# S7V10Logger.net
KiCad netlist of a schematic drawn in Altium Designer
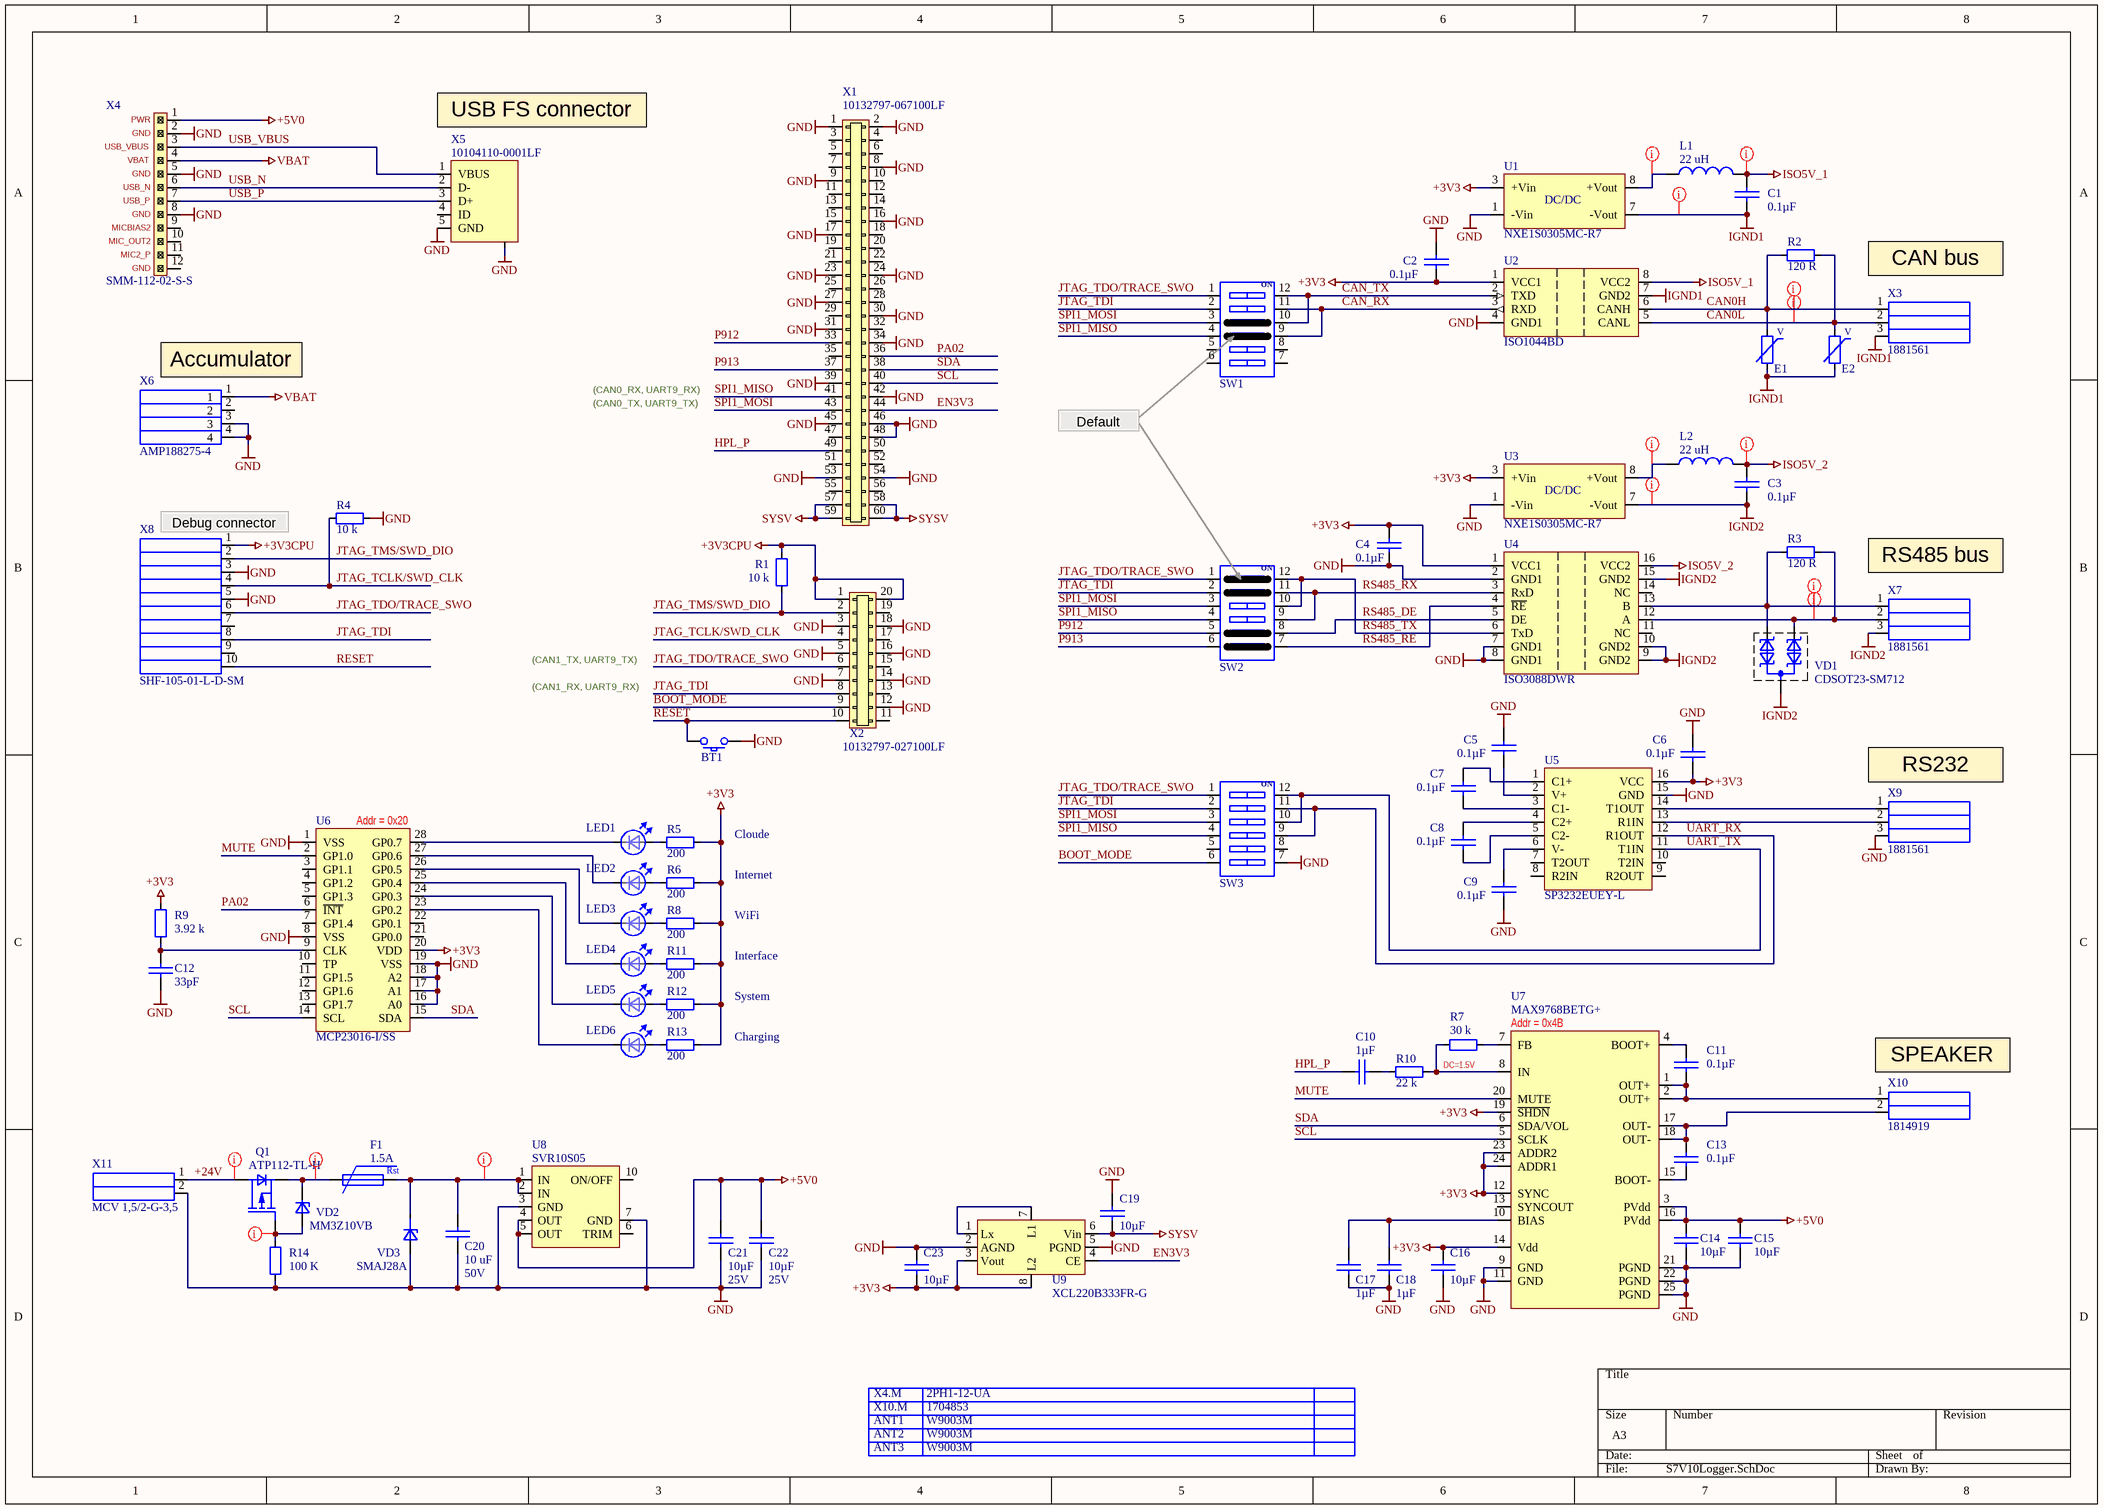
[diagram p0: S7V10Logger.SchDoc]

(export (version "E")
  (design (tool "Eeschema 10.0.6"))
  (components
    (comp (ref "ANT1")
      (value "W9003M")
      (description "CBL ASSY SMA-UMCC JACK-I-PEX 3\"")
      (fields
        (field (name "MANUFACTURER") "PulseLarsen Antennas")
        (field (name "PARTNAME") "W9003M")
        (field (name "PARTNUM") "1837-1025-ND")
      )
      (libsource (lib "ea_Mechanical") (part "BOM item"))
    )
    (comp (ref "ANT2")
      (value "W9003M")
      (description "CBL ASSY SMA-UMCC JACK-I-PEX 3\"")
      (fields
        (field (name "MANUFACTURER") "PulseLarsen Antennas")
        (field (name "PARTNAME") "W9003M")
        (field (name "PARTNUM") "1837-1025-ND")
      )
      (libsource (lib "ea_Mechanical") (part "BOM item"))
    )
    (comp (ref "ANT3")
      (value "W9003M")
      (description "CBL ASSY SMA-UMCC JACK-I-PEX 3\"")
      (fields
        (field (name "MANUFACTURER") "PulseLarsen Antennas")
        (field (name "PARTNAME") "W9003M")
        (field (name "PARTNUM") "1837-1025-ND")
      )
      (libsource (lib "ea_Mechanical") (part "BOM item"))
    )
    (comp (ref "BT1")
      (value "B3U-3000P")
      (footprint "B3U-3000P")
      (description "Tactile Switch SPST-NO Side Actuated Surface Mount, Right Angle")
      (fields
        (field (name "MANUFACTURER") "Omron Electronics Inc-EMC Div")
        (field (name "PARTNUM") "SW1022CT-ND")
      )
      (libsource (lib "ea_Buttons") (part "B3U-3000P"))
    )
    (comp (ref "C1")
      (value "0.1µF")
      (footprint "0603 CAP")
      (description "0.1µF, ±10%, 16V, X7R, 0603 (1608 Metric), -55°C ~ 125°C, -, General Purpose")
      (fields (field (name "TOLERANCE") "±10%") (field (name "MANUFACTURER") "Samsung Electro-Mechanics"))
      (libsource (lib "ea_PassivComps") (part "Capacitor"))
    )
    (comp (ref "C2")
      (value "0.1µF")
      (footprint "0603 CAP")
      (description "0.1µF, ±10%, 16V, X7R, 0603 (1608 Metric), -55°C ~ 125°C, -, General Purpose")
      (fields (field (name "TOLERANCE") "±10%") (field (name "MANUFACTURER") "Samsung Electro-Mechanics"))
      (libsource (lib "ea_PassivComps") (part "Capacitor"))
    )
    (comp (ref "C3")
      (value "0.1µF")
      (footprint "0603 CAP")
      (description "0.1µF, ±10%, 16V, X7R, 0603 (1608 Metric), -55°C ~ 125°C, -, General Purpose")
      (fields (field (name "TOLERANCE") "±10%") (field (name "MANUFACTURER") "Samsung Electro-Mechanics"))
      (libsource (lib "ea_PassivComps") (part "Capacitor"))
    )
    (comp (ref "C4")
      (value "0.1µF")
      (footprint "0603 CAP")
      (description "0.1µF, ±10%, 16V, X7R, 0603 (1608 Metric), -55°C ~ 125°C, -, General Purpose")
      (fields (field (name "TOLERANCE") "±10%") (field (name "MANUFACTURER") "Samsung Electro-Mechanics"))
      (libsource (lib "ea_PassivComps") (part "Capacitor"))
    )
    (comp (ref "C5")
      (value "0.1µF")
      (footprint "0603 CAP")
      (description "0.1µF, ±10%, 16V, X7R, 0603 (1608 Metric), -55°C ~ 125°C, -, General Purpose")
      (fields (field (name "TOLERANCE") "±10%") (field (name "MANUFACTURER") "Samsung Electro-Mechanics"))
      (libsource (lib "ea_PassivComps") (part "Capacitor"))
    )
    (comp (ref "C6")
      (value "0.1µF")
      (footprint "0603 CAP")
      (description "0.1µF, ±10%, 16V, X7R, 0603 (1608 Metric), -55°C ~ 125°C, -, General Purpose")
      (fields (field (name "TOLERANCE") "±10%") (field (name "MANUFACTURER") "Samsung Electro-Mechanics"))
      (libsource (lib "ea_PassivComps") (part "Capacitor"))
    )
    (comp (ref "C7")
      (value "0.1µF")
      (footprint "0603 CAP")
      (description "0.1µF, ±10%, 16V, X7R, 0603 (1608 Metric), -55°C ~ 125°C, -, General Purpose")
      (fields (field (name "TOLERANCE") "±10%") (field (name "MANUFACTURER") "Samsung Electro-Mechanics"))
      (libsource (lib "ea_PassivComps") (part "Capacitor"))
    )
    (comp (ref "C8")
      (value "0.1µF")
      (footprint "0603 CAP")
      (description "0.1µF, ±10%, 16V, X7R, 0603 (1608 Metric), -55°C ~ 125°C, -, General Purpose")
      (fields (field (name "TOLERANCE") "±10%") (field (name "MANUFACTURER") "Samsung Electro-Mechanics"))
      (libsource (lib "ea_PassivComps") (part "Capacitor"))
    )
    (comp (ref "C9")
      (value "0.1µF")
      (footprint "0603 CAP")
      (description "0.1µF, ±10%, 16V, X7R, 0603 (1608 Metric), -55°C ~ 125°C, -, General Purpose")
      (fields (field (name "TOLERANCE") "±10%") (field (name "MANUFACTURER") "Samsung Electro-Mechanics"))
      (libsource (lib "ea_PassivComps") (part "Capacitor"))
    )
    (comp (ref "C10")
      (value "1µF")
      (footprint "0603 CAP")
      (description "1µF, ±20%, 10V, X5R, 0603 (1608 Metric), -55°C ~ 85°C, -, General Purpose")
      (fields
        (field (name "PART NUMBER") "CL10A105MP8NNNC")
        (field (name "MANUFACTURER") "Samsung Electro-Mechanics")
      )
      (libsource (lib "ea_PassivComps") (part "Capacitor"))
    )
    (comp (ref "C11")
      (value "0.1µF")
      (footprint "0603 CAP")
      (description "0.1µF, ±10%, 16V, X7R, 0603 (1608 Metric), -55°C ~ 125°C, -, General Purpose")
      (fields (field (name "TOLERANCE") "±10%") (field (name "MANUFACTURER") "Samsung Electro-Mechanics"))
      (libsource (lib "ea_PassivComps") (part "Capacitor"))
    )
    (comp (ref "C12")
      (value "33pF")
      (footprint "0603 CAP")
      (description "33pF, ±5%, 25V, C0G, NP0, 0603 (1608 Metric), -55°C ~ 125°C, -, General Purpose")
      (fields
        (field (name "PART NUMBER") "885012006035")
        (field (name "MANUFACTURER") "Wurth Electronics Inc.")
      )
      (libsource (lib "ea_PassivComps") (part "Capacitor"))
    )
    (comp (ref "C13")
      (value "0.1µF")
      (footprint "0603 CAP")
      (description "0.1µF, ±10%, 16V, X7R, 0603 (1608 Metric), -55°C ~ 125°C, -, General Purpose")
      (fields (field (name "TOLERANCE") "±10%") (field (name "MANUFACTURER") "Samsung Electro-Mechanics"))
      (libsource (lib "ea_PassivComps") (part "Capacitor"))
    )
    (comp (ref "C14")
      (value "10µF")
      (footprint "0805 CAP")
      (description "10µF, ±20%, 16V, X5R, 0805 (2012 Metric), -55°C ~ 85°C, -, SMPS Filtering")
      (fields (field (name "PART NUMBER") "EMK212ABJ106MG-T") (field (name "MANUFACTURER") "Taiyo Yuden"))
      (libsource (lib "ea_PassivComps") (part "Capacitor"))
    )
    (comp (ref "C15")
      (value "10µF")
      (footprint "0805 CAP")
      (description "10µF, ±20%, 16V, X5R, 0805 (2012 Metric), -55°C ~ 85°C, -, SMPS Filtering")
      (fields (field (name "PART NUMBER") "EMK212ABJ106MG-T") (field (name "MANUFACTURER") "Taiyo Yuden"))
      (libsource (lib "ea_PassivComps") (part "Capacitor"))
    )
    (comp (ref "C16")
      (value "10µF")
      (footprint "0805 CAP")
      (description "10µF, ±20%, 16V, X5R, 0805 (2012 Metric), -55°C ~ 85°C, -, SMPS Filtering")
      (fields (field (name "PART NUMBER") "EMK212ABJ106MG-T") (field (name "MANUFACTURER") "Taiyo Yuden"))
      (libsource (lib "ea_PassivComps") (part "Capacitor"))
    )
    (comp (ref "C17")
      (value "1µF")
      (footprint "0603 CAP")
      (description "1µF, ±20%, 10V, X5R, 0603 (1608 Metric), -55°C ~ 85°C, -, General Purpose")
      (fields
        (field (name "PART NUMBER") "CL10A105MP8NNNC")
        (field (name "MANUFACTURER") "Samsung Electro-Mechanics")
      )
      (libsource (lib "ea_PassivComps") (part "Capacitor"))
    )
    (comp (ref "C18")
      (value "1µF")
      (footprint "0603 CAP")
      (description "1µF, ±20%, 10V, X5R, 0603 (1608 Metric), -55°C ~ 85°C, -, General Purpose")
      (fields
        (field (name "PART NUMBER") "CL10A105MP8NNNC")
        (field (name "MANUFACTURER") "Samsung Electro-Mechanics")
      )
      (libsource (lib "ea_PassivComps") (part "Capacitor"))
    )
    (comp (ref "C19")
      (value "10µF")
      (footprint "0805 CAP")
      (description "10µF, ±20%, 16V, X5R, 0805 (2012 Metric), -55°C ~ 85°C, -, SMPS Filtering")
      (fields (field (name "PART NUMBER") "EMK212ABJ106MG-T") (field (name "MANUFACTURER") "Taiyo Yuden"))
      (libsource (lib "ea_PassivComps") (part "Capacitor"))
    )
    (comp (ref "C20")
      (value "10 uF")
      (footprint "3225[1210]")
      (description "10uF, 50V, 20%, Y5V (F), 1210")
      (fields
        (field (name "MANUFACTURER") "Taiyo Yuden")
        (field (name "TOLERANCE") "20%")
        (field (name "VOLTAGE") "50V")
      )
      (libsource (lib "ea_Capacitors") (part "GRM32DF51H106ZA01L"))
    )
    (comp (ref "C21")
      (value "10µF")
      (footprint "1206 CAP")
      (description "10µF, ±10%, 25V, X5R, 1206 (3216 Metric), -55°C ~ 85°C, -, General Purpose")
      (fields
        (field (name "PART NUMBER") "CL31A106KAHNFNE")
        (field (name "MANUFACTURER") "Samsung Electro-Mechanics")
        (field (name "VOLTAGE - RATED") "25V")
      )
      (libsource (lib "ea_PassivComps") (part "Capacitor"))
    )
    (comp (ref "C22")
      (value "10µF")
      (footprint "1206 CAP")
      (description "10µF, ±10%, 25V, X5R, 1206 (3216 Metric), -55°C ~ 85°C, -, General Purpose")
      (fields
        (field (name "PART NUMBER") "CL31A106KAHNFNE")
        (field (name "MANUFACTURER") "Samsung Electro-Mechanics")
        (field (name "VOLTAGE - RATED") "25V")
      )
      (libsource (lib "ea_PassivComps") (part "Capacitor"))
    )
    (comp (ref "C23")
      (value "10µF")
      (footprint "0805 CAP")
      (description "10µF, ±20%, 16V, X5R, 0805 (2012 Metric), -55°C ~ 85°C, -, SMPS Filtering")
      (fields (field (name "PART NUMBER") "EMK212ABJ106MG-T") (field (name "MANUFACTURER") "Taiyo Yuden"))
      (libsource (lib "ea_PassivComps") (part "Capacitor"))
    )
    (comp (ref "E1")
      (value "823 560 505 60")
      (footprint "0603")
      (description "SUPPRESSOR ESD 5VDC, 56pF,  0603, -40..+85C")
      (fields (field (name "MANUFACTURER") "Würth Elektronik") (field (name "VOLTAGE") "5V"))
      (libsource (lib "ea_TVS_protection") (part "823 560 501 01"))
    )
    (comp (ref "E2")
      (value "823 560 505 60")
      (footprint "0603")
      (description "SUPPRESSOR ESD 5VDC, 56pF,  0603, -40..+85C")
      (fields (field (name "MANUFACTURER") "Würth Elektronik") (field (name "VOLTAGE") "5V"))
      (libsource (lib "ea_TVS_protection") (part "823 560 501 01"))
    )
    (comp (ref "F1")
      (value "1.5A")
      (footprint "2920 (7351 Metric)")
      (description "PTC RESETTABLE 60V 750MA, It=1.5A, 0.3s 2920(7351)")
      (fields (field (name "MANUFACTURER") "Bel Fuse Inc.") (field (name "PARTNUM") "507-1743-1-ND"))
      (libsource (lib "ea_Fuses") (part "0ZCF0075AF2C"))
    )
    (comp (ref "L1")
      (value "22 uH")
      (footprint "8200 Series Murata")
      (description "22uH, 320 mA, 0.92 Ohm, +-10%,- 40..85 C")
      (fields (field (name "MANUFACTURER") "TDK Corporation") (field (name "PARTNUM") "811-2475-1-ND"))
      (libsource (lib "ea_Inductors") (part "82223C"))
    )
    (comp (ref "L2")
      (value "22 uH")
      (footprint "8200 Series Murata")
      (description "22uH, 320 mA, 0.92 Ohm, +-10%,- 40..85 C")
      (fields (field (name "MANUFACTURER") "TDK Corporation") (field (name "PARTNUM") "811-2475-1-ND"))
      (libsource (lib "ea_Inductors") (part "82223C"))
    )
    (comp (ref "LED1")
      (value "SSL-LXA228SIC-TR31")
      (footprint "SSL-LXA228SIC-TR31")
      (description "LED RED CLEAR 2SMD REV, 20mA, 2V, 475 mcd, 1.9 mm")
      (fields (field (name "MANUFACTURER") "EVERLIGHT") (field (name "PARTNUM") "67-2243-1-ND"))
      (libsource (lib "ea_Indicators") (part "SSL-LXA228SIC-TR31"))
    )
    (comp (ref "LED2")
      (value "SSL-LXA228SIC-TR31")
      (footprint "SSL-LXA228SIC-TR31")
      (description "LED RED CLEAR 2SMD REV, 20mA, 2V, 475 mcd, 1.9 mm")
      (fields (field (name "MANUFACTURER") "EVERLIGHT") (field (name "PARTNUM") "67-2243-1-ND"))
      (libsource (lib "ea_Indicators") (part "SSL-LXA228SIC-TR31"))
    )
    (comp (ref "LED3")
      (value "SSL-LXA228SIC-TR31")
      (footprint "SSL-LXA228SIC-TR31")
      (description "LED RED CLEAR 2SMD REV, 20mA, 2V, 475 mcd, 1.9 mm")
      (fields (field (name "MANUFACTURER") "EVERLIGHT") (field (name "PARTNUM") "67-2243-1-ND"))
      (libsource (lib "ea_Indicators") (part "SSL-LXA228SIC-TR31"))
    )
    (comp (ref "LED4")
      (value "SSL-LXA228SIC-TR31")
      (footprint "SSL-LXA228SIC-TR31")
      (description "LED RED CLEAR 2SMD REV, 20mA, 2V, 475 mcd, 1.9 mm")
      (fields (field (name "MANUFACTURER") "EVERLIGHT") (field (name "PARTNUM") "67-2243-1-ND"))
      (libsource (lib "ea_Indicators") (part "SSL-LXA228SIC-TR31"))
    )
    (comp (ref "LED5")
      (value "SSL-LXA228SIC-TR31")
      (footprint "SSL-LXA228SIC-TR31")
      (description "LED RED CLEAR 2SMD REV, 20mA, 2V, 475 mcd, 1.9 mm")
      (fields (field (name "MANUFACTURER") "EVERLIGHT") (field (name "PARTNUM") "67-2243-1-ND"))
      (libsource (lib "ea_Indicators") (part "SSL-LXA228SIC-TR31"))
    )
    (comp (ref "LED6")
      (value "SSL-LXA228SIC-TR31")
      (footprint "SSL-LXA228SIC-TR31")
      (description "LED RED CLEAR 2SMD REV, 20mA, 2V, 475 mcd, 1.9 mm")
      (fields (field (name "MANUFACTURER") "EVERLIGHT") (field (name "PARTNUM") "67-2243-1-ND"))
      (libsource (lib "ea_Indicators") (part "SSL-LXA228SIC-TR31"))
    )
    (comp (ref "Q1")
      (value "ATP112-TL-H")
      (footprint "ATPAK, On Semiconductor")
      (description "P-Channel MOSFET, –25 A, –20 V, RDS(ON) = 0.04,  VGS = –10 V")
      (fields (field (name "MANUFACTURER") "ON Semiconductor") (field (name "PARTNUM") "ATP112-TL-HOSCT-ND"))
      (libsource (lib "ea_MOSFET_&_drivers") (part "ATP112-TL-H"))
    )
    (comp (ref "R1")
      (value "10 k")
      (footprint "0603")
      (fields
        (field (name "MANUFACTURER") "Bourns Inc.")
        (field (name "TOLERANCE") "±1%")
        (field (name "VOLTAGE") "75V")
      )
      (libsource (lib "") (part "Resistor_1"))
    )
    (comp (ref "R2")
      (value "120 R")
      (footprint "0603")
      (description "120 R, 1%, 0603, SMD Resistor, Taped")
      (fields (field (name "MANUFACTURER") "Vishay") (field (name "TOLERANCE") "±1%"))
      (libsource (lib "ea_Resistors") (part "RL0603E120-1"))
    )
    (comp (ref "R3")
      (value "120 R")
      (footprint "0603")
      (description "120 R, 1%, 0603, SMD Resistor, Taped")
      (fields (field (name "MANUFACTURER") "Vishay") (field (name "TOLERANCE") "±1%"))
      (libsource (lib "ea_Resistors") (part "RL0603E120-1"))
    )
    (comp (ref "R4")
      (value "10 k")
      (footprint "0603")
      (fields
        (field (name "MANUFACTURER") "Bourns Inc.")
        (field (name "TOLERANCE") "±1%")
        (field (name "VOLTAGE") "75V")
      )
      (libsource (lib "ea_PassivComps") (part "Resistor"))
    )
    (comp (ref "R5")
      (value "200")
      (footprint "0603")
      (fields
        (field (name "MANUFACTURER") "Stackpole Electronics Inc.")
        (field (name "TOLERANCE") "±1%")
        (field (name "VOLTAGE") "75V")
      )
      (libsource (lib "ea_PassivComps") (part "Resistor"))
    )
    (comp (ref "R6")
      (value "200")
      (footprint "0603")
      (fields
        (field (name "MANUFACTURER") "Stackpole Electronics Inc.")
        (field (name "TOLERANCE") "±1%")
        (field (name "VOLTAGE") "75V")
      )
      (libsource (lib "ea_PassivComps") (part "Resistor"))
    )
    (comp (ref "R7")
      (value "30 k")
      (footprint "0603")
      (fields
        (field (name "MANUFACTURER") "Stackpole Electronics Inc.")
        (field (name "TOLERANCE") "±1%")
        (field (name "VOLTAGE") "75V")
      )
      (libsource (lib "ea_PassivComps") (part "Resistor"))
    )
    (comp (ref "R8")
      (value "200")
      (footprint "0603")
      (fields
        (field (name "MANUFACTURER") "Stackpole Electronics Inc.")
        (field (name "TOLERANCE") "±1%")
        (field (name "VOLTAGE") "75V")
      )
      (libsource (lib "ea_PassivComps") (part "Resistor"))
    )
    (comp (ref "R9")
      (value "3.92 k")
      (footprint "0603")
      (fields
        (field (name "MANUFACTURER") "Stackpole Electronics Inc.")
        (field (name "TOLERANCE") "±1%")
        (field (name "VOLTAGE") "75V")
      )
      (libsource (lib "") (part "Resistor_1"))
    )
    (comp (ref "R10")
      (value "22 k")
      (footprint "0603")
      (fields
        (field (name "MANUFACTURER") "Stackpole Electronics Inc.")
        (field (name "TOLERANCE") "±1%")
        (field (name "VOLTAGE") "75V")
      )
      (libsource (lib "ea_PassivComps") (part "Resistor"))
    )
    (comp (ref "R11")
      (value "200")
      (footprint "0603")
      (fields
        (field (name "MANUFACTURER") "Stackpole Electronics Inc.")
        (field (name "TOLERANCE") "±1%")
        (field (name "VOLTAGE") "75V")
      )
      (libsource (lib "ea_PassivComps") (part "Resistor"))
    )
    (comp (ref "R12")
      (value "200")
      (footprint "0603")
      (fields
        (field (name "MANUFACTURER") "Stackpole Electronics Inc.")
        (field (name "TOLERANCE") "±1%")
        (field (name "VOLTAGE") "75V")
      )
      (libsource (lib "ea_PassivComps") (part "Resistor"))
    )
    (comp (ref "R13")
      (value "200")
      (footprint "0603")
      (fields
        (field (name "MANUFACTURER") "Stackpole Electronics Inc.")
        (field (name "TOLERANCE") "±1%")
        (field (name "VOLTAGE") "75V")
      )
      (libsource (lib "ea_PassivComps") (part "Resistor"))
    )
    (comp (ref "R14")
      (value "100 K")
      (footprint "0603")
      (description "100 K, 1%, 0603, SMD Resistor, Taped")
      (fields (field (name "MANUFACTURER") "Vishay") (field (name "TOLERANCE") "1%"))
      (libsource (lib "ea_Resistors_0603") (part "RL0603K100-1"))
    )
    (comp (ref "SW1")
      (value "CHS-06TA")
      (footprint "CHS-06TA Copal Electronics")
      (description "Dip Switch SPST 6 Position Surface Mount Slide (Standard) Actuator 100mA 6VDC")
      (fields (field (name "MANUFACTURER") "Copal Electronics Inc.") (field (name "PARTNUM") "563-1009-1-ND"))
      (libsource (lib "ea_Commutation") (part "CHS-06TA"))
    )
    (comp (ref "SW2")
      (value "CHS-06TA")
      (footprint "CHS-06TA Copal Electronics")
      (description "Dip Switch SPST 6 Position Surface Mount Slide (Standard) Actuator 100mA 6VDC")
      (fields (field (name "MANUFACTURER") "Copal Electronics Inc.") (field (name "PARTNUM") "563-1009-1-ND"))
      (libsource (lib "ea_Commutation") (part "CHS-06TA"))
    )
    (comp (ref "SW3")
      (value "CHS-06TA")
      (footprint "CHS-06TA Copal Electronics")
      (description "Dip Switch SPST 6 Position Surface Mount Slide (Standard) Actuator 100mA 6VDC")
      (fields (field (name "MANUFACTURER") "Copal Electronics Inc.") (field (name "PARTNUM") "563-1009-1-ND"))
      (libsource (lib "ea_Commutation") (part "CHS-06TA"))
    )
    (comp (ref "U1")
      (value "NXE1S0305MC-R7")
      (footprint "NXE1 Murata")
      (description "DC/DC 3V In 5V Out, 200mA, 1W, 3kV, -40..+85 C,")
      (fields
        (field (name "MANUFACTURER") "Murata Power Solutions Inc.")
        (field (name "PARTNUM") "811-3099-1-ND")
      )
      (libsource (lib "ea_PowerSources") (part "NXE1S0305MC-R7"))
    )
    (comp (ref "U2")
      (value "ISO1044BD")
      (footprint "SO-8")
      (fields (field (name "MANUFACTURER") "Texas Instruments") (field (name "PARTNUM") "296-ISO1044BD-ND"))
      (libsource (lib "ea_IC_Isolated_Interfaces") (part "ISO1044BD"))
    )
    (comp (ref "U3")
      (value "NXE1S0305MC-R7")
      (footprint "NXE1 Murata")
      (description "DC/DC 3V In 5V Out, 200mA, 1W, 3kV, -40..+85 C,")
      (fields
        (field (name "MANUFACTURER") "Murata Power Solutions Inc.")
        (field (name "PARTNUM") "811-3099-1-ND")
      )
      (libsource (lib "ea_PowerSources") (part "NXE1S0305MC-R7"))
    )
    (comp (ref "U4")
      (value "ISO3088DWR")
      (footprint "SO-G16/D10.4")
      (description "RS422, RS485 Digital Isolator 2500Vrms, 20Mbps 25kV/µs CMTI 16-SOIC, -40°C ~ 85°C")
      (fields (field (name "MANUFACTURER") "Texas Instruments") (field (name "PARTNUM") "296-41274-1-ND"))
      (libsource (lib "ea_IC_Isolated_Interfaces") (part "ISO3088DWR"))
    )
    (comp (ref "U5")
      (value "SP3232EUEY-L")
      (footprint "TSOP65P640-16AM")
      (description "IC TXRX RS232 ESD TRUE, 1 Mbps, -40+85C, 16TSSOP")
      (fields (field (name "MANUFACTURER") "Exar Corporation") (field (name "PARTNUM") "1016-1510-5-ND"))
      (libsource (lib "ea_IC_Interfaces") (part "SP3232EUEY-L"))
    )
    (comp (ref "U6")
      (value "MCP23016-I/SS")
      (footprint "MICROCHIP_SSOP28_0.65_5.3")
      (description "I2C 16-bit I/O Port Expander, 2..5.5 V, -40..+85 C")
      (fields (field (name "MANUFACTURER") "Microchip"))
      (libsource (lib "ea_IC_Interfaces") (part "MCP23016-I/SS"))
    )
    (comp (ref "U7")
      (value "MAX9768BETG+")
      (footprint "THIN QFN 24 with via")
      (description "IC Audio amp, Class D 10W, mono,  4.5..14 V, -40..+85 C, 24-TQFN")
      (fields (field (name "MANUFACTURER") "Maxim Integrated") (field (name "PARTNUM") "MAX9768BETG+-ND"))
      (libsource (lib "ea_IC_audio") (part "MAX9768BETG+"))
    )
    (comp (ref "U8")
      (value "SVR10S05")
      (footprint "SVR10S05")
      (description "Non-Isolated PoL Module DC DC Converter Output 5V 8V - Input, 1A, -40...+85 C")
      (fields (field (name "MANUFACTURER") "XP Power") (field (name "PARTNUM") "1470-SVR10S05-ND"))
      (libsource (lib "ea_IC_Power_Reg_Ref_Sw") (part "SVR10S05"))
    )
    (comp (ref "U9")
      (value "XCL220B333FR-G")
      (footprint "XCL219")
      (fields
        (field (name "MANUFACTURER") "Torex Semiconductor Ltd")
        (field (name "PARTNUM") "893-1279-1-ND")
      )
      (libsource (lib "ea_IC_Power_Reg_Ref_Sw") (part "XCL220B333FR-G"))
    )
    (comp (ref "VD1")
      (value "CDSOT23-SM712")
      (footprint "SOT23")
      (description "26V, 14V Clamp 17A (8/20µs) Ipp Tvs Diode Surface Mount SOT-23-3")
      (fields (field (name "MANUFACTURER") "Bourns Inc.") (field (name "PARTNUM") "CDSOT23-SM712CT-ND"))
      (libsource (lib "ea_TVS_protection") (part "CDSOT23-SM712"))
    )
    (comp (ref "VD2")
      (value "MM3Z10VB")
      (footprint "SOD323")
      (description "Zener diode, 10V, 18 Ohm, 200mW, SOD-323F")
      (fields (field (name "MANUFACTURER") "ON Semiconductor") (field (name "PARTNUM") "MM3Z10VBCT-ND"))
      (libsource (lib "ea_Diodes") (part "MM3Z10VB"))
    )
    (comp (ref "VD3")
      (value "SMAJ28A")
      (footprint "SMA")
      (description "DIODE TVS 28V 400W UNI 5% SMD")
      (fields (field (name "MANUFACTURER") "Bourns Inc.") (field (name "PARTNUM") "SMAJ28ABCT-ND"))
      (libsource (lib "ea_TVS_protection") (part "SMAJ28A"))
    )
    (comp (ref "X1")
      (value "10132797-067100LF")
      (footprint "10132797-067100LF")
      (description "60 Position Connector Plug, Center Strip Contacts Surface Mount Gold")
      (fields (field (name "MANUFACTURER") "Amphenol ICC (FCI)") (field (name "PARTNUM") "609-5229-1-ND"))
      (libsource (lib "ea_Connectors_0.5_mm_pitch") (part "10132797-067100LF"))
    )
    (comp (ref "X2")
      (value "10132797-027100LF")
      (footprint "10132797-027100LF")
      (description "20 Position Connector Plug, Outer Shroud Contacts Surface Mount Gold")
      (fields (field (name "MANUFACTURER") "Amphenol ICC (FCI)") (field (name "PARTNUM") "609-5232-1-ND"))
      (libsource (lib "ea_Connectors_0.5_mm_pitch") (part "10132797-027100LF"))
    )
    (comp (ref "X3")
      (value "1881561")
      (footprint "1881561")
      (description "Printed-circuit board connector - MCV 0,5/ 3-G-2,5 - 1881561")
      (fields (field (name "MANUFACTURER") "Phoenix Contact"))
      (libsource (lib "ea_Connectors_2.5_mm_pitch") (part "1881561"))
    )
    (comp (ref "X4")
      (value "SMM-112-02-S-S")
      (footprint "SMM-112-02-S-S")
      (description "12 pins, 2 mm step")
      (fields (field (name "MANUFACTURER") "Samtec Inc.") (field (name "PARTNUM") "SAM1244-12-ND"))
      (libsource (lib "S7V10_Connectors") (part "SMM-112-02-S-S"))
    )
    (comp (ref "X4.M")
      (value "2PH1-12-UA")
      (description "Connector Header Through Hole 12 position 0.079\" (2.00mm)")
      (fields
        (field (name "MANUFACTURER") "Adam Tech")
        (field (name "PARTNAME") "2PH1-12-UA")
        (field (name "PARTNUM") "2057-2PH1-12-UA-ND")
      )
      (libsource (lib "ea_Mechanical") (part "BOM item"))
    )
    (comp (ref "X5")
      (value "10104110-0001LF")
      (footprint "FCI micro USB B receptacle SMD")
      (description "USB - micro B USB 2.0 Receptacle Connector 5 Position Surface Mount, Right Angle")
      (fields (field (name "MANUFACTURER") "Amphenol FCI") (field (name "PARTNUM") "609-4052-1-ND"))
      (libsource (lib "ea_Connectors_USB") (part "10104110-0001LF"))
    )
    (comp (ref "X6")
      (value "AMP188275-4")
      (footprint "AMP188275-4")
      (description "SMD Connector Female 4-Pole")
      (fields (field (name "MANUFACTURER") "AMP") (field (name "PARTNUM") "A99473CT-ND"))
      (libsource (lib "ea_Connectors") (part "AMP188275-4"))
    )
    (comp (ref "X7")
      (value "1881561")
      (footprint "1881561")
      (description "Printed-circuit board connector - MCV 0,5/ 3-G-2,5 - 1881561")
      (fields (field (name "MANUFACTURER") "Phoenix Contact"))
      (libsource (lib "ea_Connectors_2.5_mm_pitch") (part "1881561"))
    )
    (comp (ref "X8")
      (value "SHF-105-01-L-D-SM")
      (footprint "SHF-105-01-L-D-SM")
      (description "10 Positions Header Connector 0.050\" (1.27mm) Surface Mount Gold")
      (fields (field (name "MANUFACTURER") "Samtec Inc.") (field (name "PARTNUM") "SAM14533CT-ND"))
      (libsource (lib "ea_Connectors_1.27_mm_pitch") (part "SHF-105-01-L-D-SM"))
    )
    (comp (ref "X9")
      (value "1881561")
      (footprint "1881561")
      (description "Printed-circuit board connector - MCV 0,5/ 3-G-2,5 - 1881561")
      (fields (field (name "MANUFACTURER") "Phoenix Contact"))
      (libsource (lib "ea_Connectors_2.5_mm_pitch") (part "1881561"))
    )
    (comp (ref "X10")
      (value "1814919")
      (footprint "1814919")
      (description "SSL Connector Position Header, Male Pins Board to Cable/Wire 0.098\" (2.50mm) Solder")
      (fields (field (name "MANUFACTURER") "Phoenix Contact") (field (name "PARTNUM") "277-9963-1-ND"))
      (libsource (lib "ea_Connectors_2.5_mm_pitch") (part "1814919"))
    )
    (comp (ref "X10.M")
      (value "1704853")
      (description "SSL Connector Position Plug, Female Sockets Board to Cable/Wire 0.098\" (2.50mm) Spring-Cage")
      (fields
        (field (name "MANUFACTURER") "Phoenix Contact")
        (field (name "PARTNAME") "1704853")
        (field (name "PARTNUM") "277-9949-ND")
      )
      (libsource (lib "ea_Mechanical") (part "BOM item"))
    )
    (comp (ref "X11")
      (value "MCV 1,5/2-G-3,5")
      (footprint "mcv1.5-2-g_3.5 Green  + MC 1,5 2-ST-3,5 - 1840366")
      (description "HEADER, VERTICAL, 3.5MM, 2WAY")
      (fields (field (name "MANUFACTURER") "PHOENIX CONTACT") (field (name "PARTNUM") "1843606"))
      (libsource (lib "ea_PhoenixContacts") (part "MCV 1,5/2-G-3,5"))
    )
  )
  (nets
    (net (code "1") (name "+3V3") (class "Default")
      (node (ref "C16") (pin "1") (pinfunction "1_1") (pintype "passive"))
      (node (ref "C2") (pin "1") (pinfunction "1_1") (pintype "passive"))
      (node (ref "C23") (pin "2") (pinfunction "2_2") (pintype "passive"))
      (node (ref "C4") (pin "2") (pinfunction "2_2") (pintype "passive"))
      (node (ref "C6") (pin "1") (pinfunction "1_1") (pintype "passive"))
      (node (ref "R11") (pin "2") (pinfunction "2_2") (pintype "passive"))
      (node (ref "R12") (pin "2") (pinfunction "2_2") (pintype "passive"))
      (node (ref "R13") (pin "2") (pinfunction "2_2") (pintype "passive"))
      (node (ref "R5") (pin "2") (pinfunction "2_2") (pintype "passive"))
      (node (ref "R6") (pin "2") (pinfunction "2_2") (pintype "passive"))
      (node (ref "R8") (pin "2") (pinfunction "2_2") (pintype "passive"))
      (node (ref "R9") (pin "2") (pinfunction "2_2") (pintype "passive"))
      (node (ref "U1") (pin "3") (pinfunction "+Vin_3") (pintype "passive"))
      (node (ref "U2") (pin "1") (pinfunction "VCC1_1") (pintype "power_in"))
      (node (ref "U3") (pin "3") (pinfunction "+Vin_3") (pintype "passive"))
      (node (ref "U4") (pin "1") (pinfunction "VCC1_1") (pintype "passive"))
      (node (ref "U5") (pin "16") (pinfunction "VCC_16") (pintype "passive"))
      (node (ref "U6") (pin "20") (pinfunction "VDD_20") (pintype "passive"))
      (node (ref "U7") (pin "12") (pinfunction "SYNC_12") (pintype "passive"))
      (node (ref "U7") (pin "14") (pinfunction "Vdd_14") (pintype "passive"))
      (node (ref "U7") (pin "19") (pinfunction "~{SHDN}_19") (pintype "passive"))
      (node (ref "U7") (pin "23") (pinfunction "ADDR2_23") (pintype "passive"))
      (node (ref "U7") (pin "24") (pinfunction "ADDR1_24") (pintype "passive"))
      (node (ref "U9") (pin "3") (pinfunction "Vout_3") (pintype "passive"))
      (node (ref "U9") (pin "8") (pinfunction "L2_8") (pintype "passive"))
    )
    (net (code "2") (name "+3V3CPU") (class "Default")
      (node (ref "R1") (pin "2") (pinfunction "2_2") (pintype "passive"))
      (node (ref "X2") (pin "1") (pinfunction "1_1") (pintype "passive"))
      (node (ref "X2") (pin "20") (pinfunction "11_20") (pintype "passive"))
      (node (ref "X8") (pin "1") (pinfunction "1_1") (pintype "passive"))
    )
    (net (code "3") (name "+5V0") (class "Default")
      (node (ref "C14") (pin "1") (pinfunction "1_1") (pintype "passive"))
      (node (ref "C15") (pin "1") (pinfunction "1_1") (pintype "passive"))
      (node (ref "C21") (pin "1") (pinfunction "1_1") (pintype "passive"))
      (node (ref "C22") (pin "1") (pinfunction "1_1") (pintype "passive"))
      (node (ref "U7") (pin "16") (pinfunction "PVdd_16") (pintype "passive"))
      (node (ref "U7") (pin "3") (pinfunction "PVdd_3") (pintype "passive"))
      (node (ref "U8") (pin "4") (pinfunction "OUT_4") (pintype "power_in"))
      (node (ref "U8") (pin "5") (pinfunction "OUT_5") (pintype "power_in"))
      (node (ref "X4") (pin "1") (pinfunction "1_1") (pintype "passive"))
    )
    (net (code "4") (name "/+24V") (class "Default")
      (node (ref "Q1") (pin "4") (pinfunction "D_4") (pintype "passive"))
      (node (ref "X11") (pin "1") (pinfunction "1_1") (pintype "passive"))
    )
    (net (code "5") (name "/BOOT_MODE") (class "Default")
      (node (ref "SW3") (pin "6") (pinfunction "6_6") (pintype "passive"))
      (node (ref "X2") (pin "9") (pinfunction "5_9") (pintype "passive"))
    )
    (net (code "6") (name "/CAN0H") (class "Default")
      (node (ref "E1") (pin "2") (pinfunction "2_2") (pintype "passive"))
      (node (ref "R2") (pin "2") (pinfunction "2_2") (pintype "passive"))
      (node (ref "U2") (pin "6") (pinfunction "CANH_6") (pintype "bidirectional"))
      (node (ref "X3") (pin "1") (pinfunction "1_1") (pintype "passive"))
    )
    (net (code "7") (name "/CAN0L") (class "Default")
      (node (ref "E2") (pin "2") (pinfunction "2_2") (pintype "passive"))
      (node (ref "R2") (pin "1") (pinfunction "1_1") (pintype "passive"))
      (node (ref "U2") (pin "5") (pinfunction "CANL_5") (pintype "bidirectional"))
      (node (ref "X3") (pin "2") (pinfunction "2_2") (pintype "passive"))
    )
    (net (code "8") (name "/CAN_RX") (class "Default")
      (node (ref "SW1") (pin "11") (pinfunction "11_11") (pintype "passive"))
      (node (ref "SW1") (pin "9") (pinfunction "9_9") (pintype "passive"))
      (node (ref "U2") (pin "3") (pinfunction "RXD_3") (pintype "output"))
    )
    (net (code "9") (name "/CAN_TX") (class "Default")
      (node (ref "SW1") (pin "10") (pinfunction "10_10") (pintype "passive"))
      (node (ref "SW1") (pin "12") (pinfunction "12_12") (pintype "passive"))
      (node (ref "U2") (pin "2") (pinfunction "TXD_2") (pintype "input"))
    )
    (net (code "10") (name "/EN3V3") (class "Default")
      (node (ref "U9") (pin "4") (pinfunction "CE_4") (pintype "passive"))
      (node (ref "X1") (pin "44") (pinfunction "23_44") (pintype "passive"))
    )
    (net (code "11") (name "/HPL_P") (class "Default")
      (node (ref "C10") (pin "1") (pinfunction "1_1") (pintype "passive"))
      (node (ref "X1") (pin "49") (pinfunction "25_49") (pintype "passive"))
    )
    (net (code "12") (name "/JTAG_TCLK{slash}SWD_CLK") (class "Default")
      (node (ref "R4") (pin "1") (pinfunction "1_1") (pintype "passive"))
      (node (ref "X2") (pin "4") (pinfunction "3_4") (pintype "passive"))
      (node (ref "X8") (pin "4") (pinfunction "4_4") (pintype "passive"))
    )
    (net (code "13") (name "/JTAG_TDI") (class "Default")
      (node (ref "SW1") (pin "2") (pinfunction "2_2") (pintype "passive"))
      (node (ref "SW2") (pin "2") (pinfunction "2_2") (pintype "passive"))
      (node (ref "SW3") (pin "2") (pinfunction "2_2") (pintype "passive"))
      (node (ref "X2") (pin "8") (pinfunction "5_8") (pintype "passive"))
      (node (ref "X8") (pin "8") (pinfunction "8_8") (pintype "passive"))
    )
    (net (code "14") (name "/JTAG_TDO{slash}TRACE_SWO") (class "Default")
      (node (ref "SW1") (pin "1") (pinfunction "1_1") (pintype "passive"))
      (node (ref "SW2") (pin "1") (pinfunction "1_1") (pintype "passive"))
      (node (ref "SW3") (pin "1") (pinfunction "1_1") (pintype "passive"))
      (node (ref "X2") (pin "6") (pinfunction "4_6") (pintype "passive"))
      (node (ref "X8") (pin "6") (pinfunction "6_6") (pintype "passive"))
    )
    (net (code "15") (name "/JTAG_TMS{slash}SWD_DIO") (class "Default")
      (node (ref "R1") (pin "1") (pinfunction "1_1") (pintype "passive"))
      (node (ref "X2") (pin "2") (pinfunction "2_2") (pintype "passive"))
      (node (ref "X8") (pin "2") (pinfunction "2_2") (pintype "passive"))
    )
    (net (code "16") (name "/MUTE") (class "Default")
      (node (ref "U6") (pin "2") (pinfunction "GP1.0_2") (pintype "passive"))
      (node (ref "U7") (pin "20") (pinfunction "MUTE_20") (pintype "passive"))
    )
    (net (code "17") (name "/P912") (class "Default")
      (node (ref "SW2") (pin "5") (pinfunction "5_5") (pintype "passive"))
      (node (ref "X1") (pin "33") (pinfunction "17_33") (pintype "passive"))
    )
    (net (code "18") (name "/P913") (class "Default")
      (node (ref "SW2") (pin "6") (pinfunction "6_6") (pintype "passive"))
      (node (ref "X1") (pin "37") (pinfunction "19_37") (pintype "passive"))
    )
    (net (code "19") (name "/PA02") (class "Default")
      (node (ref "U6") (pin "6") (pinfunction "~{INT}_6") (pintype "passive"))
      (node (ref "X1") (pin "36") (pinfunction "19_36") (pintype "passive"))
    )
    (net (code "20") (name "/RESET") (class "Default")
      (node (ref "BT1") (pin "2") (pinfunction "2_2") (pintype "passive"))
      (node (ref "X2") (pin "10") (pinfunction "6_10") (pintype "passive"))
      (node (ref "X8") (pin "10") (pinfunction "10_10") (pintype "passive"))
    )
    (net (code "21") (name "/RS485_DE") (class "Default")
      (node (ref "SW2") (pin "8") (pinfunction "8_8") (pintype "passive"))
      (node (ref "U4") (pin "5") (pinfunction "DE_5") (pintype "passive"))
    )
    (net (code "22") (name "/RS485_RE") (class "Default")
      (node (ref "SW2") (pin "7") (pinfunction "7_7") (pintype "passive"))
      (node (ref "U4") (pin "4") (pinfunction "~{RE}_4") (pintype "passive"))
    )
    (net (code "23") (name "/RS485_RX") (class "Default")
      (node (ref "SW2") (pin "11") (pinfunction "11_11") (pintype "passive"))
      (node (ref "SW2") (pin "9") (pinfunction "9_9") (pintype "passive"))
      (node (ref "U4") (pin "3") (pinfunction "RxD_3") (pintype "passive"))
    )
    (net (code "24") (name "/RS485_TX") (class "Default")
      (node (ref "SW2") (pin "10") (pinfunction "10_10") (pintype "passive"))
      (node (ref "SW2") (pin "12") (pinfunction "12_12") (pintype "passive"))
      (node (ref "U4") (pin "6") (pinfunction "TxD_6") (pintype "passive"))
    )
    (net (code "25") (name "/SCL") (class "Default")
      (node (ref "U6") (pin "14") (pinfunction "SCL_14") (pintype "passive"))
      (node (ref "U7") (pin "5") (pinfunction "SCLK_5") (pintype "passive"))
      (node (ref "X1") (pin "40") (pinfunction "21_40") (pintype "passive"))
    )
    (net (code "26") (name "/SDA") (class "Default")
      (node (ref "U6") (pin "15") (pinfunction "SDA_15") (pintype "passive"))
      (node (ref "U7") (pin "6") (pinfunction "SDA/VOL_6") (pintype "passive"))
      (node (ref "X1") (pin "38") (pinfunction "20_38") (pintype "passive"))
    )
    (net (code "27") (name "/SPI1_MISO") (class "Default")
      (node (ref "SW1") (pin "4") (pinfunction "4_4") (pintype "passive"))
      (node (ref "SW2") (pin "4") (pinfunction "4_4") (pintype "passive"))
      (node (ref "SW3") (pin "4") (pinfunction "4_4") (pintype "passive"))
      (node (ref "X1") (pin "41") (pinfunction "21_41") (pintype "passive"))
    )
    (net (code "28") (name "/SPI1_MOSI") (class "Default")
      (node (ref "SW1") (pin "3") (pinfunction "3_3") (pintype "passive"))
      (node (ref "SW2") (pin "3") (pinfunction "3_3") (pintype "passive"))
      (node (ref "SW3") (pin "3") (pinfunction "3_3") (pintype "passive"))
      (node (ref "X1") (pin "43") (pinfunction "22_43") (pintype "passive"))
    )
    (net (code "29") (name "/UART_RX") (class "Default")
      (node (ref "SW3") (pin "11") (pinfunction "11_11") (pintype "passive"))
      (node (ref "SW3") (pin "9") (pinfunction "9_9") (pintype "passive"))
      (node (ref "U5") (pin "12") (pinfunction "R1OUT_12") (pintype "passive"))
    )
    (net (code "30") (name "/UART_TX") (class "Default")
      (node (ref "SW3") (pin "10") (pinfunction "10_10") (pintype "passive"))
      (node (ref "SW3") (pin "12") (pinfunction "12_12") (pintype "passive"))
      (node (ref "U5") (pin "11") (pinfunction "T1IN_11") (pintype "passive"))
    )
    (net (code "31") (name "/USB_N") (class "Default")
      (node (ref "X4") (pin "6") (pinfunction "6_6") (pintype "passive"))
      (node (ref "X5") (pin "2") (pinfunction "D-_2") (pintype "bidirectional"))
    )
    (net (code "32") (name "/USB_P") (class "Default")
      (node (ref "X4") (pin "7") (pinfunction "7_7") (pintype "passive"))
      (node (ref "X5") (pin "3") (pinfunction "D+_3") (pintype "bidirectional"))
    )
    (net (code "33") (name "/USB_VBUS") (class "Default")
      (node (ref "X4") (pin "3") (pinfunction "3_3") (pintype "passive"))
      (node (ref "X5") (pin "1") (pinfunction "VBUS_1") (pintype "power_in"))
    )
    (net (code "34") (name "GND") (class "Default")
      (node (ref "BT1") (pin "1") (pinfunction "1_1") (pintype "passive"))
      (node (ref "C12") (pin "2") (pinfunction "2_2") (pintype "passive"))
      (node (ref "C14") (pin "2") (pinfunction "2_2") (pintype "passive"))
      (node (ref "C15") (pin "2") (pinfunction "2_2") (pintype "passive"))
      (node (ref "C16") (pin "2") (pinfunction "2_2") (pintype "passive"))
      (node (ref "C17") (pin "2") (pinfunction "2_2") (pintype "passive"))
      (node (ref "C18") (pin "2") (pinfunction "2_2") (pintype "passive"))
      (node (ref "C19") (pin "1") (pinfunction "1_1") (pintype "passive"))
      (node (ref "C2") (pin "2") (pinfunction "2_2") (pintype "passive"))
      (node (ref "C20") (pin "2") (pinfunction "2_2") (pintype "passive"))
      (node (ref "C21") (pin "2") (pinfunction "2_2") (pintype "passive"))
      (node (ref "C22") (pin "2") (pinfunction "2_2") (pintype "passive"))
      (node (ref "C23") (pin "1") (pinfunction "1_1") (pintype "passive"))
      (node (ref "C4") (pin "1") (pinfunction "1_1") (pintype "passive"))
      (node (ref "C5") (pin "2") (pinfunction "2_2") (pintype "passive"))
      (node (ref "C6") (pin "2") (pinfunction "2_2") (pintype "passive"))
      (node (ref "C9") (pin "1") (pinfunction "1_1") (pintype "passive"))
      (node (ref "R14") (pin "1") (pinfunction "1_1") (pintype "passive"))
      (node (ref "R4") (pin "2") (pinfunction "2_2") (pintype "passive"))
      (node (ref "SW3") (pin "7") (pinfunction "7_7") (pintype "passive"))
      (node (ref "U1") (pin "1") (pinfunction "-Vin_1") (pintype "passive"))
      (node (ref "U2") (pin "4") (pinfunction "GND1_4") (pintype "power_in"))
      (node (ref "U3") (pin "1") (pinfunction "-Vin_1") (pintype "passive"))
      (node (ref "U4") (pin "2") (pinfunction "GND1_2") (pintype "passive"))
      (node (ref "U4") (pin "7") (pinfunction "GND1_7") (pintype "passive"))
      (node (ref "U4") (pin "8") (pinfunction "GND1_8") (pintype "passive"))
      (node (ref "U5") (pin "15") (pinfunction "GND_15") (pintype "passive"))
      (node (ref "U6") (pin "1") (pinfunction "VSS_1") (pintype "passive"))
      (node (ref "U6") (pin "16") (pinfunction "A0_16") (pintype "passive"))
      (node (ref "U6") (pin "17") (pinfunction "A1_17") (pintype "passive"))
      (node (ref "U6") (pin "18") (pinfunction "A2_18") (pintype "passive"))
      (node (ref "U6") (pin "19") (pinfunction "VSS_19") (pintype "passive"))
      (node (ref "U6") (pin "8") (pinfunction "VSS_8") (pintype "passive"))
      (node (ref "U7") (pin "11") (pinfunction "GND_11") (pintype "passive"))
      (node (ref "U7") (pin "21") (pinfunction "PGND_21") (pintype "passive"))
      (node (ref "U7") (pin "22") (pinfunction "PGND_22") (pintype "passive"))
      (node (ref "U7") (pin "25") (pinfunction "PGND_25") (pintype "passive"))
      (node (ref "U7") (pin "9") (pinfunction "GND_9") (pintype "passive"))
      (node (ref "U8") (pin "3") (pinfunction "GND_3") (pintype "power_in"))
      (node (ref "U8") (pin "7") (pinfunction "GND_7") (pintype "power_in"))
      (node (ref "U9") (pin "2") (pinfunction "AGND_2") (pintype "passive"))
      (node (ref "U9") (pin "5") (pinfunction "PGND_5") (pintype "passive"))
      (node (ref "VD3") (pin "2") (pinfunction "2_2") (pintype "passive"))
      (node (ref "X1") (pin "1") (pinfunction "1_1") (pintype "passive"))
      (node (ref "X1") (pin "16") (pinfunction "9_16") (pintype "passive"))
      (node (ref "X1") (pin "17") (pinfunction "9_17") (pintype "passive"))
      (node (ref "X1") (pin "2") (pinfunction "2_2") (pintype "passive"))
      (node (ref "X1") (pin "23") (pinfunction "12_23") (pintype "passive"))
      (node (ref "X1") (pin "24") (pinfunction "13_24") (pintype "passive"))
      (node (ref "X1") (pin "27") (pinfunction "14_27") (pintype "passive"))
      (node (ref "X1") (pin "30") (pinfunction "16_30") (pintype "passive"))
      (node (ref "X1") (pin "31") (pinfunction "16_31") (pintype "passive"))
      (node (ref "X1") (pin "34") (pinfunction "18_34") (pintype "passive"))
      (node (ref "X1") (pin "39") (pinfunction "20_39") (pintype "passive"))
      (node (ref "X1") (pin "42") (pinfunction "22_42") (pintype "passive"))
      (node (ref "X1") (pin "45") (pinfunction "23_45") (pintype "passive"))
      (node (ref "X1") (pin "46") (pinfunction "24_46") (pintype "passive"))
      (node (ref "X1") (pin "48") (pinfunction "25_48") (pintype "passive"))
      (node (ref "X1") (pin "53") (pinfunction "27_53") (pintype "passive"))
      (node (ref "X1") (pin "54") (pinfunction "28_54") (pintype "passive"))
      (node (ref "X1") (pin "8") (pinfunction "5_8") (pintype "passive"))
      (node (ref "X1") (pin "9") (pinfunction "5_9") (pintype "passive"))
      (node (ref "X11") (pin "2") (pinfunction "2_2") (pintype "passive"))
      (node (ref "X2") (pin "12") (pinfunction "7_12") (pintype "passive"))
      (node (ref "X2") (pin "14") (pinfunction "8_14") (pintype "passive"))
      (node (ref "X2") (pin "16") (pinfunction "9_16") (pintype "passive"))
      (node (ref "X2") (pin "18") (pinfunction "10_18") (pintype "passive"))
      (node (ref "X2") (pin "3") (pinfunction "2_3") (pintype "passive"))
      (node (ref "X2") (pin "5") (pinfunction "3_5") (pintype "passive"))
      (node (ref "X2") (pin "7") (pinfunction "4_7") (pintype "passive"))
      (node (ref "X4") (pin "2") (pinfunction "2_2") (pintype "passive"))
      (node (ref "X4") (pin "5") (pinfunction "5_5") (pintype "passive"))
      (node (ref "X4") (pin "8") (pinfunction "8_8") (pintype "passive"))
      (node (ref "X5") (pin "5") (pinfunction "GND_5") (pintype "power_in"))
      (node (ref "X5") (pin "G1") (pinfunction "CASE_G1") (pintype "power_in"))
      (node (ref "X6") (pin "3") (pinfunction "3_3") (pintype "passive"))
      (node (ref "X6") (pin "4") (pinfunction "4_4") (pintype "passive"))
      (node (ref "X8") (pin "3") (pinfunction "3_3") (pintype "passive"))
      (node (ref "X8") (pin "5") (pinfunction "5_5") (pintype "passive"))
      (node (ref "X9") (pin "3") (pinfunction "3_3") (pintype "passive"))
    )
    (net (code "35") (name "IGND1") (class "Default")
      (node (ref "C1") (pin "1") (pinfunction "1_1") (pintype "passive"))
      (node (ref "E1") (pin "1") (pinfunction "1_1") (pintype "passive"))
      (node (ref "E2") (pin "1") (pinfunction "1_1") (pintype "passive"))
      (node (ref "U1") (pin "7") (pinfunction "-Vout_7") (pintype "passive"))
      (node (ref "U2") (pin "7") (pinfunction "GND2_7") (pintype "power_in"))
      (node (ref "X3") (pin "3") (pinfunction "3_3") (pintype "passive"))
    )
    (net (code "36") (name "IGND2") (class "Default")
      (node (ref "C3") (pin "1") (pinfunction "1_1") (pintype "passive"))
      (node (ref "U3") (pin "7") (pinfunction "-Vout_7") (pintype "passive"))
      (node (ref "U4") (pin "10") (pinfunction "GND2_10") (pintype "passive"))
      (node (ref "U4") (pin "15") (pinfunction "GND2_15") (pintype "passive"))
      (node (ref "U4") (pin "9") (pinfunction "GND2_9") (pintype "passive"))
      (node (ref "VD1") (pin "3") (pintype "passive"))
      (node (ref "X7") (pin "3") (pinfunction "3_3") (pintype "passive"))
    )
    (net (code "37") (name "ISO5V_1") (class "Default")
      (node (ref "C1") (pin "2") (pinfunction "2_2") (pintype "passive"))
      (node (ref "L1") (pin "2") (pinfunction "2_2") (pintype "passive"))
      (node (ref "U2") (pin "8") (pinfunction "VCC2_8") (pintype "power_in"))
    )
    (net (code "38") (name "ISO5V_2") (class "Default")
      (node (ref "C3") (pin "2") (pinfunction "2_2") (pintype "passive"))
      (node (ref "L2") (pin "2") (pinfunction "2_2") (pintype "passive"))
      (node (ref "U4") (pin "16") (pinfunction "VCC2_16") (pintype "passive"))
    )
    (net (code "39") (name "Net-(C10-Pad2)") (class "Default")
      (node (ref "C10") (pin "2") (pinfunction "2_2") (pintype "passive"))
      (node (ref "R10") (pin "1") (pinfunction "1_1") (pintype "passive"))
    )
    (net (code "40") (name "Net-(C11-Pad1)") (class "Default")
      (node (ref "C11") (pin "1") (pinfunction "1_1") (pintype "passive"))
      (node (ref "U7") (pin "1") (pinfunction "OUT+_1") (pintype "passive"))
      (node (ref "U7") (pin "2") (pinfunction "OUT+_2") (pintype "passive"))
      (node (ref "X10") (pin "1") (pinfunction "1_1") (pintype "passive"))
    )
    (net (code "41") (name "Net-(C13-Pad2)") (class "Default")
      (node (ref "C13") (pin "2") (pinfunction "2_2") (pintype "passive"))
      (node (ref "U7") (pin "17") (pinfunction "OUT-_17") (pintype "passive"))
      (node (ref "U7") (pin "18") (pinfunction "OUT-_18") (pintype "passive"))
      (node (ref "X10") (pin "2") (pinfunction "2_2") (pintype "passive"))
    )
    (net (code "42") (name "Net-(C20-Pad1)") (class "Default")
      (node (ref "C20") (pin "1") (pinfunction "1_1") (pintype "passive"))
      (node (ref "F1") (pin "2") (pinfunction "2_2") (pintype "passive"))
      (node (ref "U8") (pin "1") (pinfunction "IN_1") (pintype "power_in"))
      (node (ref "U8") (pin "2") (pinfunction "IN_2") (pintype "power_in"))
      (node (ref "VD3") (pin "1") (pinfunction "1_1") (pintype "passive"))
    )
    (net (code "43") (name "Net-(LED1-Pad1)") (class "Default")
      (node (ref "LED1") (pin "1") (pinfunction "1_1") (pintype "passive"))
      (node (ref "R5") (pin "1") (pinfunction "1_1") (pintype "passive"))
    )
    (net (code "44") (name "Net-(LED2-Pad1)") (class "Default")
      (node (ref "LED2") (pin "1") (pinfunction "1_1") (pintype "passive"))
      (node (ref "R6") (pin "1") (pinfunction "1_1") (pintype "passive"))
    )
    (net (code "45") (name "Net-(LED3-Pad1)") (class "Default")
      (node (ref "LED3") (pin "1") (pinfunction "1_1") (pintype "passive"))
      (node (ref "R8") (pin "1") (pinfunction "1_1") (pintype "passive"))
    )
    (net (code "46") (name "Net-(LED4-Pad1)") (class "Default")
      (node (ref "LED4") (pin "1") (pinfunction "1_1") (pintype "passive"))
      (node (ref "R11") (pin "1") (pinfunction "1_1") (pintype "passive"))
    )
    (net (code "47") (name "Net-(LED5-Pad1)") (class "Default")
      (node (ref "LED5") (pin "1") (pinfunction "1_1") (pintype "passive"))
      (node (ref "R12") (pin "1") (pinfunction "1_1") (pintype "passive"))
    )
    (net (code "48") (name "Net-(LED6-Pad1)") (class "Default")
      (node (ref "LED6") (pin "1") (pinfunction "1_1") (pintype "passive"))
      (node (ref "R13") (pin "1") (pinfunction "1_1") (pintype "passive"))
    )
    (net (code "49") (name "Net-(Q1-G)") (class "Default")
      (node (ref "Q1") (pin "1") (pinfunction "G_1") (pintype "passive"))
      (node (ref "R14") (pin "2") (pinfunction "2_2") (pintype "passive"))
      (node (ref "VD2") (pin "1") (pinfunction "1_1") (pintype "passive"))
    )
    (net (code "50") (name "Net-(Q1-S)") (class "Default")
      (node (ref "F1") (pin "1") (pinfunction "1_1") (pintype "passive"))
      (node (ref "Q1") (pin "3") (pinfunction "S_3") (pintype "passive"))
      (node (ref "VD2") (pin "2") (pinfunction "2_2") (pintype "passive"))
    )
    (net (code "51") (name "Net-(U1-+Vout)") (class "Default")
      (node (ref "L1") (pin "1") (pinfunction "1_1") (pintype "passive"))
      (node (ref "U1") (pin "8") (pinfunction "+Vout_8") (pintype "passive"))
    )
    (net (code "52") (name "Net-(U3-+Vout)") (class "Default")
      (node (ref "L2") (pin "1") (pinfunction "1_1") (pintype "passive"))
      (node (ref "U3") (pin "8") (pinfunction "+Vout_8") (pintype "passive"))
    )
    (net (code "53") (name "Net-(U4-A)") (class "Default")
      (node (ref "R3") (pin "1") (pinfunction "1_1") (pintype "passive"))
      (node (ref "U4") (pin "12") (pinfunction "A_12") (pintype "passive"))
      (node (ref "VD1") (pin "1") (pintype "passive"))
      (node (ref "X7") (pin "2") (pinfunction "2_2") (pintype "passive"))
    )
    (net (code "54") (name "Net-(U4-B)") (class "Default")
      (node (ref "R3") (pin "2") (pinfunction "2_2") (pintype "passive"))
      (node (ref "U4") (pin "13") (pinfunction "B_13") (pintype "passive"))
      (node (ref "VD1") (pin "2") (pintype "passive"))
      (node (ref "X7") (pin "1") (pinfunction "1_1") (pintype "passive"))
    )
    (net (code "55") (name "Net-(U5-C1+)") (class "Default")
      (node (ref "C7") (pin "2") (pinfunction "2_2") (pintype "passive"))
      (node (ref "U5") (pin "1") (pinfunction "C1+_1") (pintype "passive"))
    )
    (net (code "56") (name "Net-(U5-C1-)") (class "Default")
      (node (ref "C7") (pin "1") (pinfunction "1_1") (pintype "passive"))
      (node (ref "U5") (pin "3") (pinfunction "C1-_3") (pintype "passive"))
    )
    (net (code "57") (name "Net-(U5-C2+)") (class "Default")
      (node (ref "C8") (pin "2") (pinfunction "2_2") (pintype "passive"))
      (node (ref "U5") (pin "4") (pinfunction "C2+_4") (pintype "passive"))
    )
    (net (code "58") (name "Net-(U5-C2-)") (class "Default")
      (node (ref "C8") (pin "1") (pinfunction "1_1") (pintype "passive"))
      (node (ref "U5") (pin "5") (pinfunction "C2-_5") (pintype "passive"))
    )
    (net (code "59") (name "Net-(U5-R1IN)") (class "Default")
      (node (ref "U5") (pin "13") (pinfunction "R1IN_13") (pintype "passive"))
      (node (ref "X9") (pin "2") (pinfunction "2_2") (pintype "passive"))
    )
    (net (code "60") (name "Net-(U5-T1OUT)") (class "Default")
      (node (ref "U5") (pin "14") (pinfunction "T1OUT_14") (pintype "passive"))
      (node (ref "X9") (pin "1") (pinfunction "1_1") (pintype "passive"))
    )
    (net (code "61") (name "Net-(U5-V+)") (class "Default")
      (node (ref "C5") (pin "1") (pinfunction "1_1") (pintype "passive"))
      (node (ref "U5") (pin "2") (pinfunction "V+_2") (pintype "passive"))
    )
    (net (code "62") (name "Net-(U5-V-)") (class "Default")
      (node (ref "C9") (pin "2") (pinfunction "2_2") (pintype "passive"))
      (node (ref "U5") (pin "6") (pinfunction "V-_6") (pintype "passive"))
    )
    (net (code "63") (name "Net-(U6-CLK)") (class "Default")
      (node (ref "C12") (pin "1") (pinfunction "1_1") (pintype "passive"))
      (node (ref "R9") (pin "1") (pinfunction "1_1") (pintype "passive"))
      (node (ref "U6") (pin "9") (pinfunction "CLK_9") (pintype "passive"))
    )
    (net (code "64") (name "Net-(U6-GP0.2)") (class "Default")
      (node (ref "LED6") (pin "2") (pinfunction "2_2") (pintype "passive"))
      (node (ref "U6") (pin "23") (pinfunction "GP0.2_23") (pintype "passive"))
    )
    (net (code "65") (name "Net-(U6-GP0.3)") (class "Default")
      (node (ref "LED5") (pin "2") (pinfunction "2_2") (pintype "passive"))
      (node (ref "U6") (pin "24") (pinfunction "GP0.3_24") (pintype "passive"))
    )
    (net (code "66") (name "Net-(U6-GP0.4)") (class "Default")
      (node (ref "LED4") (pin "2") (pinfunction "2_2") (pintype "passive"))
      (node (ref "U6") (pin "25") (pinfunction "GP0.4_25") (pintype "passive"))
    )
    (net (code "67") (name "Net-(U6-GP0.5)") (class "Default")
      (node (ref "LED3") (pin "2") (pinfunction "2_2") (pintype "passive"))
      (node (ref "U6") (pin "26") (pinfunction "GP0.5_26") (pintype "passive"))
    )
    (net (code "68") (name "Net-(U6-GP0.6)") (class "Default")
      (node (ref "LED2") (pin "2") (pinfunction "2_2") (pintype "passive"))
      (node (ref "U6") (pin "27") (pinfunction "GP0.6_27") (pintype "passive"))
    )
    (net (code "69") (name "Net-(U6-GP0.7)") (class "Default")
      (node (ref "LED1") (pin "2") (pinfunction "2_2") (pintype "passive"))
      (node (ref "U6") (pin "28") (pinfunction "GP0.7_28") (pintype "passive"))
    )
    (net (code "70") (name "Net-(U7-BIAS)") (class "Default")
      (node (ref "C17") (pin "1") (pinfunction "1_1") (pintype "passive"))
      (node (ref "C18") (pin "1") (pinfunction "1_1") (pintype "passive"))
      (node (ref "U7") (pin "10") (pinfunction "BIAS_10") (pintype "passive"))
    )
    (net (code "71") (name "Net-(U7-BOOT+)") (class "Default")
      (node (ref "C11") (pin "2") (pinfunction "2_2") (pintype "passive"))
      (node (ref "U7") (pin "4") (pinfunction "BOOT+_4") (pintype "passive"))
    )
    (net (code "72") (name "Net-(U7-BOOT-)") (class "Default")
      (node (ref "C13") (pin "1") (pinfunction "1_1") (pintype "passive"))
      (node (ref "U7") (pin "15") (pinfunction "BOOT-_15") (pintype "passive"))
    )
    (net (code "73") (name "Net-(U7-FB)") (class "Default")
      (node (ref "R7") (pin "2") (pinfunction "2_2") (pintype "passive"))
      (node (ref "U7") (pin "7") (pinfunction "FB_7") (pintype "passive"))
    )
    (net (code "74") (name "Net-(U7-IN)") (class "Default")
      (node (ref "R10") (pin "2") (pinfunction "2_2") (pintype "passive"))
      (node (ref "R7") (pin "1") (pinfunction "1_1") (pintype "passive"))
      (node (ref "U7") (pin "8") (pinfunction "IN_8") (pintype "passive"))
    )
    (net (code "75") (name "Net-(U9-L1)") (class "Default")
      (node (ref "U9") (pin "1") (pinfunction "Lx_1") (pintype "passive"))
      (node (ref "U9") (pin "7") (pinfunction "L1_7") (pintype "passive"))
    )
    (net (code "76") (name "SYSV") (class "Default")
      (node (ref "C19") (pin "2") (pinfunction "2_2") (pintype "passive"))
      (node (ref "U9") (pin "6") (pinfunction "Vin_6") (pintype "passive"))
      (node (ref "X1") (pin "57") (pinfunction "29_57") (pintype "passive"))
      (node (ref "X1") (pin "58") (pinfunction "30_58") (pintype "passive"))
      (node (ref "X1") (pin "59") (pinfunction "30_59") (pintype "passive"))
      (node (ref "X1") (pin "60") (pinfunction "31_60") (pintype "passive"))
    )
    (net (code "77") (name "VBAT") (class "Default")
      (node (ref "X4") (pin "4") (pinfunction "4_4") (pintype "passive"))
      (node (ref "X6") (pin "1") (pinfunction "1_1") (pintype "passive"))
    )
    (net (code "78") (name "unconnected-(SW1-Pad5)") (class "Default")
      (node (ref "SW1") (pin "5") (pinfunction "5_5") (pintype "passive"))
    )
    (net (code "79") (name "unconnected-(SW1-Pad6)") (class "Default")
      (node (ref "SW1") (pin "6") (pinfunction "6_6") (pintype "passive"))
    )
    (net (code "80") (name "unconnected-(SW1-Pad7)") (class "Default")
      (node (ref "SW1") (pin "7") (pinfunction "7_7") (pintype "passive"))
    )
    (net (code "81") (name "unconnected-(SW1-Pad8)") (class "Default")
      (node (ref "SW1") (pin "8") (pinfunction "8_8") (pintype "passive"))
    )
    (net (code "82") (name "unconnected-(SW3-Pad5)") (class "Default")
      (node (ref "SW3") (pin "5") (pinfunction "5_5") (pintype "passive"))
    )
    (net (code "83") (name "unconnected-(SW3-Pad8)") (class "Default")
      (node (ref "SW3") (pin "8") (pinfunction "8_8") (pintype "passive"))
    )
    (net (code "84") (name "unconnected-(U4-NC-Pad11)") (class "Default")
      (node (ref "U4") (pin "11") (pinfunction "NC_11") (pintype "passive"))
    )
    (net (code "85") (name "unconnected-(U4-NC-Pad14)") (class "Default")
      (node (ref "U4") (pin "14") (pinfunction "NC_14") (pintype "passive"))
    )
    (net (code "86") (name "unconnected-(U5-R2IN-Pad8)") (class "Default")
      (node (ref "U5") (pin "8") (pinfunction "R2IN_8") (pintype "passive"))
    )
    (net (code "87") (name "unconnected-(U5-R2OUT-Pad9)") (class "Default")
      (node (ref "U5") (pin "9") (pinfunction "R2OUT_9") (pintype "passive"))
    )
    (net (code "88") (name "unconnected-(U5-T2IN-Pad10)") (class "Default")
      (node (ref "U5") (pin "10") (pinfunction "T2IN_10") (pintype "passive"))
    )
    (net (code "89") (name "unconnected-(U5-T2OUT-Pad7)") (class "Default")
      (node (ref "U5") (pin "7") (pinfunction "T2OUT_7") (pintype "passive"))
    )
    (net (code "90") (name "unconnected-(U6-GP0.0-Pad21)") (class "Default")
      (node (ref "U6") (pin "21") (pinfunction "GP0.0_21") (pintype "passive"))
    )
    (net (code "91") (name "unconnected-(U6-GP0.1-Pad22)") (class "Default")
      (node (ref "U6") (pin "22") (pinfunction "GP0.1_22") (pintype "passive"))
    )
    (net (code "92") (name "unconnected-(U6-GP1.1-Pad3)") (class "Default")
      (node (ref "U6") (pin "3") (pinfunction "GP1.1_3") (pintype "passive"))
    )
    (net (code "93") (name "unconnected-(U6-GP1.2-Pad4)") (class "Default")
      (node (ref "U6") (pin "4") (pinfunction "GP1.2_4") (pintype "passive"))
    )
    (net (code "94") (name "unconnected-(U6-GP1.3-Pad5)") (class "Default")
      (node (ref "U6") (pin "5") (pinfunction "GP1.3_5") (pintype "passive"))
    )
    (net (code "95") (name "unconnected-(U6-GP1.4-Pad7)") (class "Default")
      (node (ref "U6") (pin "7") (pinfunction "GP1.4_7") (pintype "passive"))
    )
    (net (code "96") (name "unconnected-(U6-GP1.5-Pad11)") (class "Default")
      (node (ref "U6") (pin "11") (pinfunction "GP1.5_11") (pintype "passive"))
    )
    (net (code "97") (name "unconnected-(U6-GP1.6-Pad12)") (class "Default")
      (node (ref "U6") (pin "12") (pinfunction "GP1.6_12") (pintype "passive"))
    )
    (net (code "98") (name "unconnected-(U6-GP1.7-Pad13)") (class "Default")
      (node (ref "U6") (pin "13") (pinfunction "GP1.7_13") (pintype "passive"))
    )
    (net (code "99") (name "unconnected-(U6-TP-Pad10)") (class "Default")
      (node (ref "U6") (pin "10") (pinfunction "TP_10") (pintype "passive"))
    )
    (net (code "100") (name "unconnected-(U7-SYNCOUT-Pad13)") (class "Default")
      (node (ref "U7") (pin "13") (pinfunction "SYNCOUT_13") (pintype "passive"))
    )
    (net (code "101") (name "unconnected-(U8-ON{slash}OFF-Pad10)") (class "Default")
      (node (ref "U8") (pin "10") (pinfunction "ON/OFF_10") (pintype "power_in"))
    )
    (net (code "102") (name "unconnected-(U8-TRIM-Pad6)") (class "Default")
      (node (ref "U8") (pin "6") (pinfunction "TRIM_6") (pintype "power_in"))
    )
    (net (code "103") (name "unconnected-(X1-2-Pad3)") (class "Default")
      (node (ref "X1") (pin "3") (pinfunction "2_3") (pintype "passive"))
    )
    (net (code "104") (name "unconnected-(X1-3-Pad4)") (class "Default")
      (node (ref "X1") (pin "4") (pinfunction "3_4") (pintype "passive"))
    )
    (net (code "105") (name "unconnected-(X1-3-Pad5)") (class "Default")
      (node (ref "X1") (pin "5") (pinfunction "3_5") (pintype "passive"))
    )
    (net (code "106") (name "unconnected-(X1-4-Pad6)") (class "Default")
      (node (ref "X1") (pin "6") (pinfunction "4_6") (pintype "passive"))
    )
    (net (code "107") (name "unconnected-(X1-4-Pad7)") (class "Default")
      (node (ref "X1") (pin "7") (pinfunction "4_7") (pintype "passive"))
    )
    (net (code "108") (name "unconnected-(X1-6-Pad10)") (class "Default")
      (node (ref "X1") (pin "10") (pinfunction "6_10") (pintype "passive"))
    )
    (net (code "109") (name "unconnected-(X1-6-Pad11)") (class "Default")
      (node (ref "X1") (pin "11") (pinfunction "6_11") (pintype "passive"))
    )
    (net (code "110") (name "unconnected-(X1-7-Pad12)") (class "Default")
      (node (ref "X1") (pin "12") (pinfunction "7_12") (pintype "passive"))
    )
    (net (code "111") (name "unconnected-(X1-7-Pad13)") (class "Default")
      (node (ref "X1") (pin "13") (pinfunction "7_13") (pintype "passive"))
    )
    (net (code "112") (name "unconnected-(X1-8-Pad14)") (class "Default")
      (node (ref "X1") (pin "14") (pinfunction "8_14") (pintype "passive"))
    )
    (net (code "113") (name "unconnected-(X1-8-Pad15)") (class "Default")
      (node (ref "X1") (pin "15") (pinfunction "8_15") (pintype "passive"))
    )
    (net (code "114") (name "unconnected-(X1-10-Pad18)") (class "Default")
      (node (ref "X1") (pin "18") (pinfunction "10_18") (pintype "passive"))
    )
    (net (code "115") (name "unconnected-(X1-10-Pad19)") (class "Default")
      (node (ref "X1") (pin "19") (pinfunction "10_19") (pintype "passive"))
    )
    (net (code "116") (name "unconnected-(X1-11-Pad20)") (class "Default")
      (node (ref "X1") (pin "20") (pinfunction "11_20") (pintype "passive"))
    )
    (net (code "117") (name "unconnected-(X1-11-Pad21)") (class "Default")
      (node (ref "X1") (pin "21") (pinfunction "11_21") (pintype "passive"))
    )
    (net (code "118") (name "unconnected-(X1-12-Pad22)") (class "Default")
      (node (ref "X1") (pin "22") (pinfunction "12_22") (pintype "passive"))
    )
    (net (code "119") (name "unconnected-(X1-13-Pad25)") (class "Default")
      (node (ref "X1") (pin "25") (pinfunction "13_25") (pintype "passive"))
    )
    (net (code "120") (name "unconnected-(X1-14-Pad26)") (class "Default")
      (node (ref "X1") (pin "26") (pinfunction "14_26") (pintype "passive"))
    )
    (net (code "121") (name "unconnected-(X1-15-Pad28)") (class "Default")
      (node (ref "X1") (pin "28") (pinfunction "15_28") (pintype "passive"))
    )
    (net (code "122") (name "unconnected-(X1-15-Pad29)") (class "Default")
      (node (ref "X1") (pin "29") (pinfunction "15_29") (pintype "passive"))
    )
    (net (code "123") (name "unconnected-(X1-17-Pad32)") (class "Default")
      (node (ref "X1") (pin "32") (pinfunction "17_32") (pintype "passive"))
    )
    (net (code "124") (name "unconnected-(X1-18-Pad35)") (class "Default")
      (node (ref "X1") (pin "35") (pinfunction "18_35") (pintype "passive"))
    )
    (net (code "125") (name "unconnected-(X1-24-Pad47)") (class "Default")
      (node (ref "X1") (pin "47") (pinfunction "24_47") (pintype "passive"))
    )
    (net (code "126") (name "unconnected-(X1-26-Pad50)") (class "Default")
      (node (ref "X1") (pin "50") (pinfunction "26_50") (pintype "passive"))
    )
    (net (code "127") (name "unconnected-(X1-26-Pad51)") (class "Default")
      (node (ref "X1") (pin "51") (pinfunction "26_51") (pintype "passive"))
    )
    (net (code "128") (name "unconnected-(X1-27-Pad52)") (class "Default")
      (node (ref "X1") (pin "52") (pinfunction "27_52") (pintype "passive"))
    )
    (net (code "129") (name "unconnected-(X1-28-Pad55)") (class "Default")
      (node (ref "X1") (pin "55") (pinfunction "28_55") (pintype "passive"))
    )
    (net (code "130") (name "unconnected-(X1-29-Pad56)") (class "Default")
      (node (ref "X1") (pin "56") (pinfunction "29_56") (pintype "passive"))
    )
    (net (code "131") (name "unconnected-(X2-6-Pad11)") (class "Default")
      (node (ref "X2") (pin "11") (pinfunction "6_11") (pintype "passive"))
    )
    (net (code "132") (name "unconnected-(X2-7-Pad13)") (class "Default")
      (node (ref "X2") (pin "13") (pinfunction "7_13") (pintype "passive"))
    )
    (net (code "133") (name "unconnected-(X2-8-Pad15)") (class "Default")
      (node (ref "X2") (pin "15") (pinfunction "8_15") (pintype "passive"))
    )
    (net (code "134") (name "unconnected-(X2-9-Pad17)") (class "Default")
      (node (ref "X2") (pin "17") (pinfunction "9_17") (pintype "passive"))
    )
    (net (code "135") (name "unconnected-(X2-10-Pad19)") (class "Default")
      (node (ref "X2") (pin "19") (pinfunction "10_19") (pintype "passive"))
    )
    (net (code "136") (name "unconnected-(X4-Pad9)") (class "Default")
      (node (ref "X4") (pin "9") (pinfunction "9_9") (pintype "passive"))
    )
    (net (code "137") (name "unconnected-(X4-Pad10)") (class "Default")
      (node (ref "X4") (pin "10") (pinfunction "10_10") (pintype "passive"))
    )
    (net (code "138") (name "unconnected-(X4-Pad11)") (class "Default")
      (node (ref "X4") (pin "11") (pinfunction "11_11") (pintype "passive"))
    )
    (net (code "139") (name "unconnected-(X4-Pad12)") (class "Default")
      (node (ref "X4") (pin "12") (pinfunction "12_12") (pintype "passive"))
    )
    (net (code "140") (name "unconnected-(X5-ID-Pad4)") (class "Default")
      (node (ref "X5") (pin "4") (pinfunction "ID_4") (pintype "passive"))
    )
    (net (code "141") (name "unconnected-(X6-Pad2)") (class "Default")
      (node (ref "X6") (pin "2") (pinfunction "2_2") (pintype "passive"))
    )
    (net (code "142") (name "unconnected-(X8-Pad7)") (class "Default")
      (node (ref "X8") (pin "7") (pinfunction "7_7") (pintype "passive"))
    )
    (net (code "143") (name "unconnected-(X8-Pad9)") (class "Default")
      (node (ref "X8") (pin "9") (pinfunction "9_9") (pintype "passive"))
    )
  )
)
